# OpenPLCv0_2_0_BinaryOut.net
KiCad netlist of a schematic drawn in Altium Designer
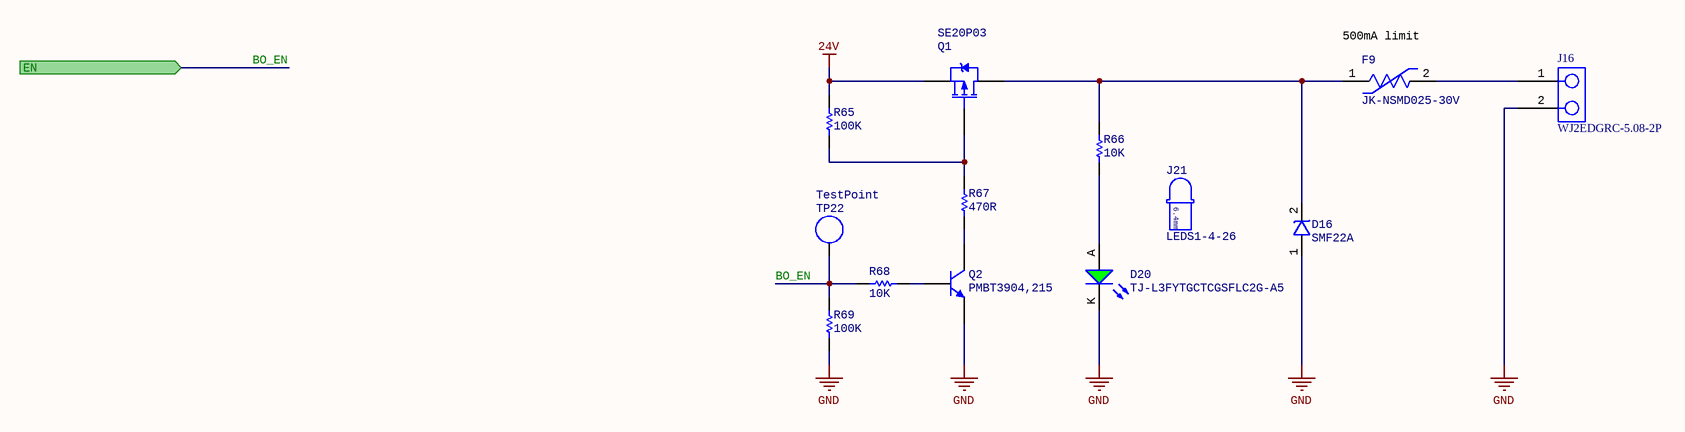
[diagram p0: OpenPLCv0.2.0_BinaryOut.SchDoc]

(export (version "E")
  (design (tool "Eeschema 10.0.6"))
  (components
    (comp (ref "D16")
      (value "SMF22A")
      (footprint "SOD-123FL")
      (description "Unidirectional 22V 24.4V 35.5V 5.6A SOD-123F TVS RoHS")
      (libsource (lib "BrauV2") (part "SMF22A"))
    )
    (comp (ref "D20")
      (value "TJ-L3FYTGCTCGSFLC2G-A5")
      (footprint "LED_3MM_SPACED_6.4MM_GREEN")
      (description "LED 3mm Green 515nm~530nm 1.8V~3.6V Through Hole Light Emitting Diodes (LED) RoHS C330751")
      (libsource (lib "BrauV2_Diode") (part "TJ-L3FYTGCTCGSFLC2G-A5"))
    )
    (comp (ref "F9")
      (value "JK-NSMD025-30V")
      (footprint "SMD_RES_1206(3216)_N")
      (description "Polymeric 30V 500mA 0.08s 700mΩ 1206 PTC Resettable Fuses RoHS")
      (libsource (lib "BrauV2_Resistor") (part "JK-NSMD025-30V"))
    )
    (comp (ref "J16")
      (value "WJ2EDGRC-5.08-2P")
      (footprint "796638-2_BoardEdgeAlt")
      (description "Covered（4Sided） 2 1 0.200\"（5.08mm） 2 P=5.08mm Pluggable System Terminal Block RoHS")
      (libsource (lib "OpenPLCv0.2.0_Connector") (part "WJ2EDGRC-5.08-2P"))
    )
    (comp (ref "J21")
      (value "LEDS1-4-26")
      (footprint "3MM_LED_SPACER_6.4MM")
      (description "3mm LED spacer 6.4mm height")
      (libsource (lib "BrauV2_Misc") (part "LEDS1-4-26"))
    )
    (comp (ref "Q1")
      (value "SE20P03")
      (footprint "TO-252")
      (description "P-Channel 30V 19A 3V @ 250uA 50mΩ @ 10A,10V 30W TO-252-2(DPAK) MOSFET RoHS")
      (libsource (lib "BrauV2_Transistor") (part "SE20P03"))
    )
    (comp (ref "Q2")
      (value "PMBT3904,215")
      (footprint "SOT23-3")
      (description "NPN 200mA 40V 250mW SOT-23(SOT-23-3) Transistors (NPN/PNP) RoHS")
      (libsource (lib "BrauV2_Transistor") (part "PMBT3904,215"))
    )
    (comp (ref "R65")
      (value "RC0402FR-07100KL")
      (footprint "SMD_RES_0402(1005)_N")
      (description "100kΩ ±1% 1/16W ±100ppm/℃ 0402 Chip Resistor - Surface Mount RoHS")
      (fields (field (name "TOLERANCE") "1%") (field (name "RESISTANCE") "100K"))
      (libsource (lib "BrauV2_Resistor") (part "100K 0402 1% 1/16W"))
    )
    (comp (ref "R66")
      (value "RC0402FR-0710KL")
      (footprint "SMD_RES_0402(1005)_N")
      (description "10kΩ ±1% 1/16W ±100ppm/℃ 0402 Chip Resistor - Surface Mount RoHS")
      (fields (field (name "TOLERANCE") "1%") (field (name "RESISTANCE") "10K"))
      (libsource (lib "BrauV2_Resistor") (part "10K 0402 1% 1/16W"))
    )
    (comp (ref "R67")
      (value "RC0402FR-07470RL")
      (footprint "SMD_RES_0402(1005)_N")
      (description "470Ω ±1% 1/16W ±100ppm/℃ 0402 Chip Resistor - Surface Mount RoHS")
      (fields (field (name "TOLERANCE") "1%") (field (name "RESISTANCE") "470R"))
      (libsource (lib "BrauV2_Resistor") (part "470R 0402 1% 1W"))
    )
    (comp (ref "R68")
      (value "RC0402FR-0710KL")
      (footprint "SMD_RES_0402(1005)_N")
      (description "10kΩ ±1% 1/16W ±100ppm/℃ 0402 Chip Resistor - Surface Mount RoHS")
      (fields (field (name "TOLERANCE") "1%") (field (name "RESISTANCE") "10K"))
      (libsource (lib "BrauV2_Resistor") (part "10K 0402 1% 1/16W"))
    )
    (comp (ref "R69")
      (value "RC0402FR-07100KL")
      (footprint "SMD_RES_0402(1005)_N")
      (description "100kΩ ±1% 1/16W ±100ppm/℃ 0402 Chip Resistor - Surface Mount RoHS")
      (fields (field (name "TOLERANCE") "1%") (field (name "RESISTANCE") "100K"))
      (libsource (lib "BrauV2_Resistor") (part "100K 0402 1% 1/16W"))
    )
    (comp (ref "TP22")
      (value "TestPoint")
      (footprint "Pad")
      (libsource (lib "OpenPLCv0.2.0_Misc") (part "Test point"))
    )
  )
  (nets
    (net (code "1") (name "/BO_EN") (class "Default")
      (node (ref "R68") (pin "2") (pinfunction "2_2") (pintype "passive"))
      (node (ref "R69") (pin "1") (pinfunction "1_1") (pintype "passive"))
      (node (ref "TP22") (pin "1") (pinfunction "1_1") (pintype "passive"))
    )
    (net (code "2") (name "24V") (class "Default")
      (node (ref "Q1") (pin "3") (pinfunction "S_3") (pintype "passive"))
      (node (ref "R65") (pin "2") (pinfunction "2_2") (pintype "passive"))
    )
    (net (code "3") (name "GND") (class "Default")
      (node (ref "D16") (pin "1") (pinfunction "ANODE_1") (pintype "passive"))
      (node (ref "D20") (pin "K") (pinfunction "K_K") (pintype "passive"))
      (node (ref "J16") (pin "2") (pinfunction "2_2") (pintype "passive"))
      (node (ref "Q2") (pin "2") (pinfunction "E_2") (pintype "passive"))
      (node (ref "R69") (pin "2") (pinfunction "2_2") (pintype "passive"))
    )
    (net (code "4") (name "Net-(D16-CATHODE)") (class "Default")
      (node (ref "D16") (pin "2") (pinfunction "CATHODE_2") (pintype "passive"))
      (node (ref "F9") (pin "1") (pinfunction "1_1") (pintype "passive"))
      (node (ref "Q1") (pin "2") (pinfunction "D_2") (pintype "passive"))
      (node (ref "R66") (pin "2") (pinfunction "2_2") (pintype "passive"))
    )
    (net (code "5") (name "Net-(D20-PadA)") (class "Default")
      (node (ref "D20") (pin "A") (pinfunction "A_A") (pintype "passive"))
      (node (ref "R66") (pin "1") (pinfunction "1_1") (pintype "passive"))
    )
    (net (code "6") (name "Net-(F9-Pad2)") (class "Default")
      (node (ref "F9") (pin "2") (pinfunction "2_2") (pintype "passive"))
      (node (ref "J16") (pin "1") (pinfunction "1_1") (pintype "passive"))
    )
    (net (code "7") (name "Net-(Q1-G)") (class "Default")
      (node (ref "Q1") (pin "1") (pinfunction "G_1") (pintype "passive"))
      (node (ref "R65") (pin "1") (pinfunction "1_1") (pintype "passive"))
      (node (ref "R67") (pin "2") (pinfunction "2_2") (pintype "passive"))
    )
    (net (code "8") (name "Net-(Q2-B)") (class "Default")
      (node (ref "Q2") (pin "1") (pinfunction "B_1") (pintype "passive"))
      (node (ref "R68") (pin "1") (pinfunction "1_1") (pintype "passive"))
    )
    (net (code "9") (name "Net-(Q2-C)") (class "Default")
      (node (ref "Q2") (pin "3") (pinfunction "C_3") (pintype "passive"))
      (node (ref "R67") (pin "1") (pinfunction "1_1") (pintype "passive"))
    )
  )
)
